# Schematic.net
KiCad netlist of a schematic drawn in EAGLE
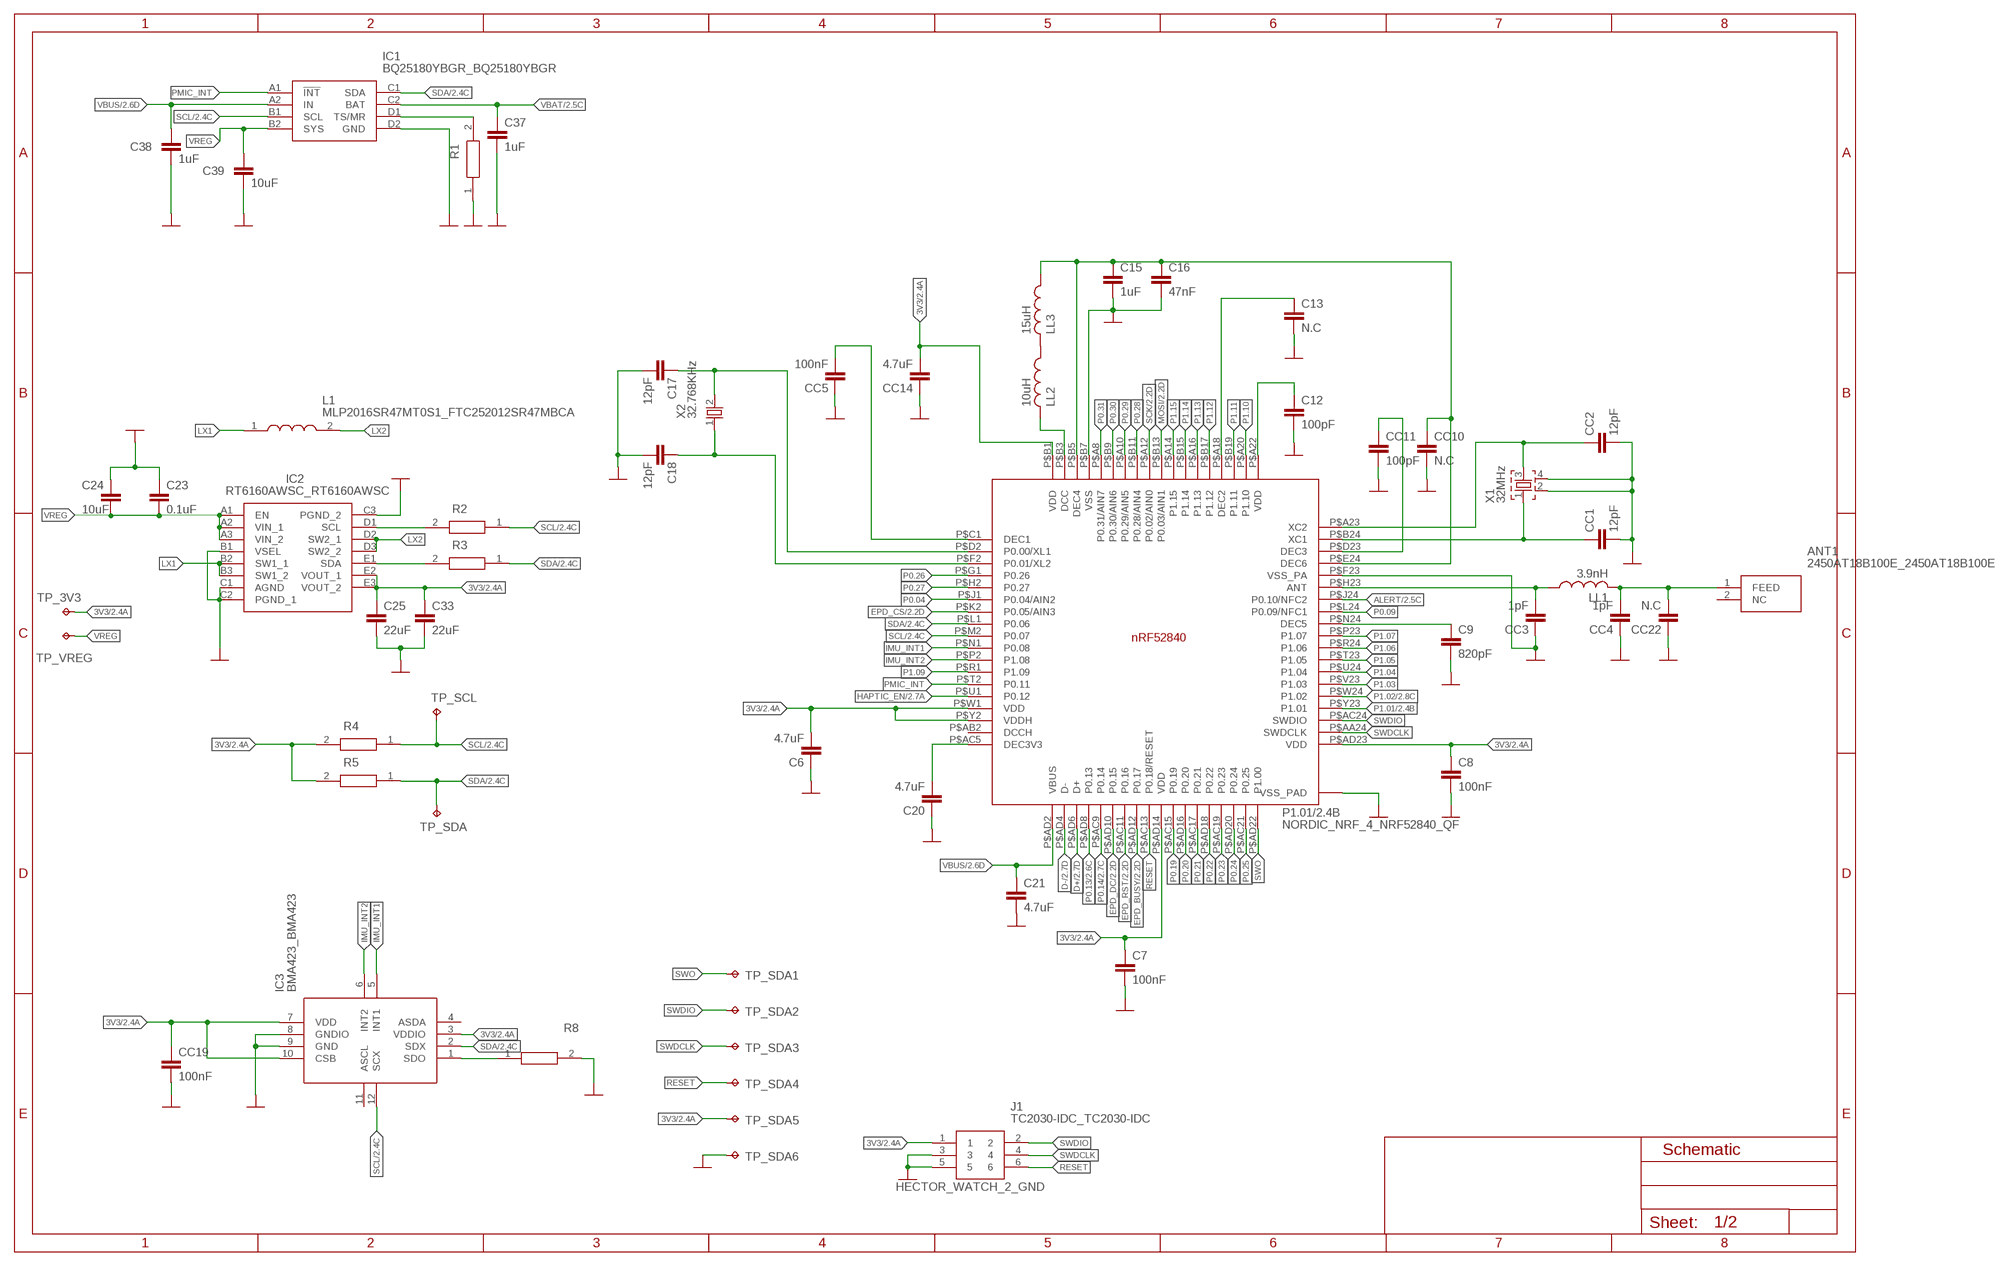
[diagram p0: schematic, sheet 1]
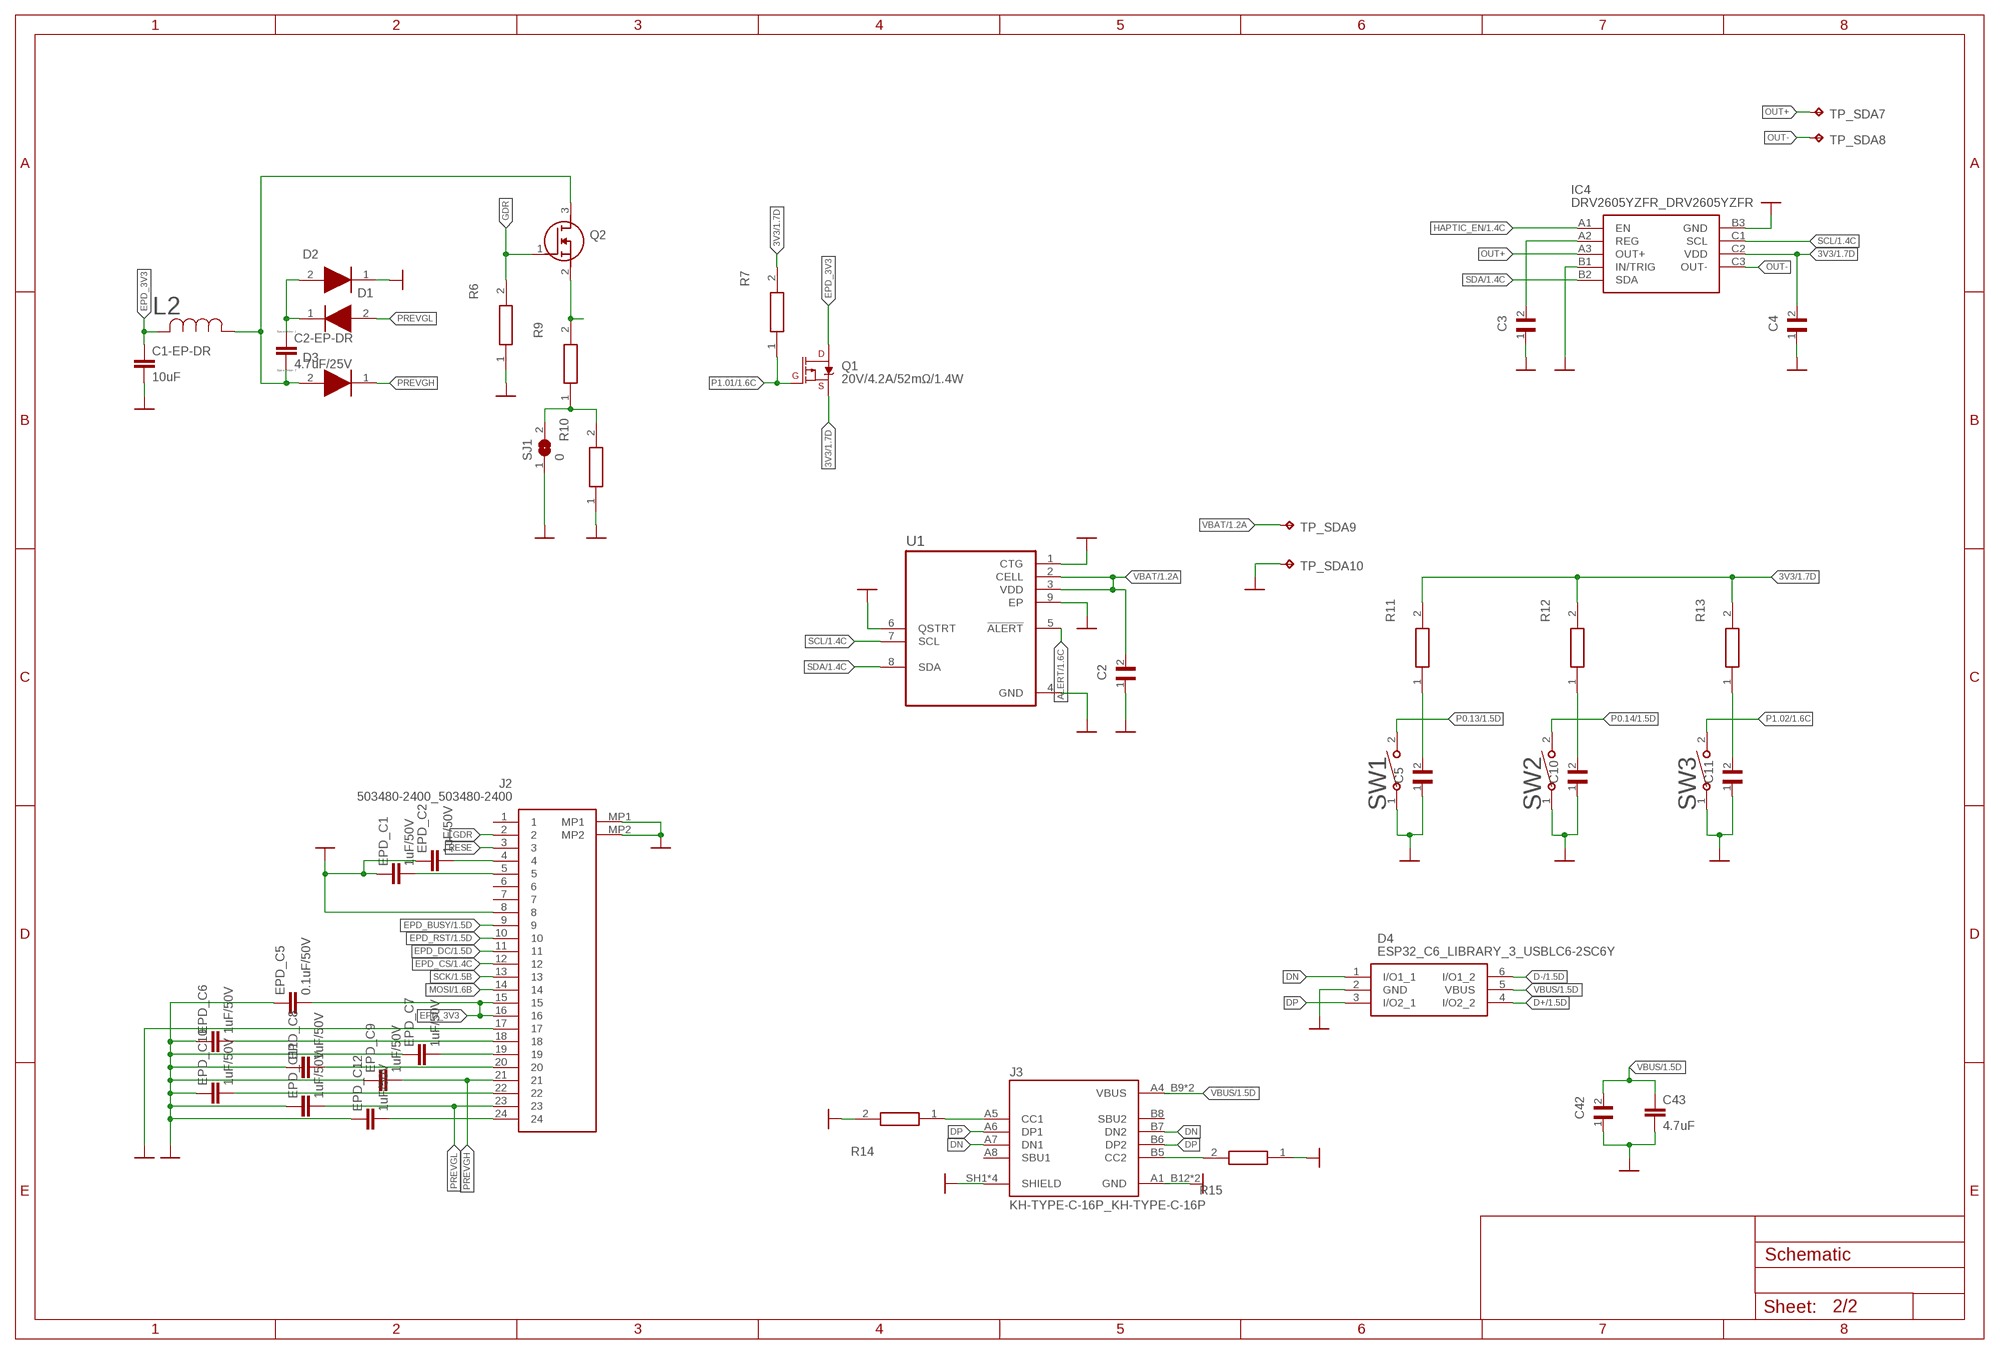
[diagram p1: schematic, sheet 2]

(export (version "E")
  (design (tool "Eeschema 10.0.6"))
  (components
    (comp (ref "ANT1")
      (value "2450AT18B100E_2450AT18B100E")
      (footprint "eagle-import:2450AT18B100E_ANTC3216X140N")
      (fields
        (field (name "ARROW_PART_NUMBER") "2450AT18B100E")
        (field (name "MOUSER_PART_NUMBER") "609-2450AT18B100E")
      )
      (libsource (lib "eagle-import") (part "2450AT18B100E_2450AT18B100E"))
    )
    (comp (ref "C6")
      (value "4.7uF")
      (footprint "eagle-import:NORDIC_NRF_3_RESC0402_M")
      (libsource (lib "eagle-import") (part "NORDIC_NRF_3_CAPACITOR_0402_M"))
    )
    (comp (ref "C7")
      (value "100nF")
      (footprint "eagle-import:NORDIC_NRF_3_RESC0402_M")
      (libsource (lib "eagle-import") (part "NORDIC_NRF_3_CAPACITOR_0402_M"))
    )
    (comp (ref "C8")
      (value "100nF")
      (footprint "eagle-import:NORDIC_NRF_3_RESC0402_M")
      (libsource (lib "eagle-import") (part "NORDIC_NRF_3_CAPACITOR_0402_M"))
    )
    (comp (ref "C9")
      (value "820pF")
      (footprint "eagle-import:NORDIC_NRF_3_RESC0402_M")
      (libsource (lib "eagle-import") (part "NORDIC_NRF_3_CAPACITOR_0402_M"))
    )
    (comp (ref "C12")
      (value "100pF")
      (footprint "eagle-import:NORDIC_NRF_3_RESC0402_M")
      (libsource (lib "eagle-import") (part "NORDIC_NRF_3_CAPACITOR_0402_M"))
    )
    (comp (ref "C13")
      (value "N.C")
      (footprint "eagle-import:NORDIC_NRF_3_RESC0402_M")
      (libsource (lib "eagle-import") (part "NORDIC_NRF_3_CAPACITOR_0402_M"))
    )
    (comp (ref "C15")
      (value "1uF")
      (footprint "eagle-import:NORDIC_NRF_3_RESC0402_M")
      (libsource (lib "eagle-import") (part "NORDIC_NRF_3_CAPACITOR_0402_M"))
    )
    (comp (ref "C16")
      (value "47nF")
      (footprint "eagle-import:NORDIC_NRF_3_RESC0402_M")
      (libsource (lib "eagle-import") (part "NORDIC_NRF_3_CAPACITOR_0402_M"))
    )
    (comp (ref "C17")
      (value "12pF")
      (footprint "eagle-import:NORDIC_NRF_3_RESC0402_M")
      (libsource (lib "eagle-import") (part "NORDIC_NRF_3_CAPACITOR_0402_M"))
    )
    (comp (ref "C18")
      (value "12pF")
      (footprint "eagle-import:NORDIC_NRF_3_RESC0402_M")
      (libsource (lib "eagle-import") (part "NORDIC_NRF_3_CAPACITOR_0402_M"))
    )
    (comp (ref "C20")
      (value "4.7uF")
      (footprint "eagle-import:NORDIC_NRF_3_RESC0402_M")
      (libsource (lib "eagle-import") (part "NORDIC_NRF_3_CAPACITOR_0402_M"))
    )
    (comp (ref "C21")
      (value "4.7uF")
      (footprint "eagle-import:NORDIC_NRF_3_RESC0402_M")
      (libsource (lib "eagle-import") (part "NORDIC_NRF_3_CAPACITOR_0402_M"))
    )
    (comp (ref "C23")
      (value "0.1uF")
      (footprint "eagle-import:NORDIC_NRF_3_RESC0402_M")
      (libsource (lib "eagle-import") (part "NORDIC_NRF_3_CAPACITOR_0402_M"))
    )
    (comp (ref "C24")
      (value "10uF")
      (footprint "eagle-import:NORDIC_NRF_3_RESC0402_M")
      (libsource (lib "eagle-import") (part "NORDIC_NRF_3_CAPACITOR_0402_M"))
    )
    (comp (ref "C25")
      (value "22uF")
      (footprint "eagle-import:NORDIC_NRF_3_RESC0402_M")
      (libsource (lib "eagle-import") (part "NORDIC_NRF_3_CAPACITOR_0402_M"))
    )
    (comp (ref "C33")
      (value "22uF")
      (footprint "eagle-import:NORDIC_NRF_3_RESC0402_M")
      (libsource (lib "eagle-import") (part "NORDIC_NRF_3_CAPACITOR_0402_M"))
    )
    (comp (ref "C37")
      (value "1uF")
      (footprint "eagle-import:NORDIC_NRF_3_RESC0402_M")
      (libsource (lib "eagle-import") (part "NORDIC_NRF_3_CAPACITOR_0402_M"))
    )
    (comp (ref "C38")
      (value "1uF")
      (footprint "eagle-import:NORDIC_NRF_3_RESC0402_M")
      (libsource (lib "eagle-import") (part "NORDIC_NRF_3_CAPACITOR_0402_M"))
    )
    (comp (ref "C39")
      (value "10uF")
      (footprint "eagle-import:NORDIC_NRF_3_RESC0402_M")
      (libsource (lib "eagle-import") (part "NORDIC_NRF_3_CAPACITOR_0402_M"))
    )
    (comp (ref "CC1")
      (value "12pF")
      (footprint "eagle-import:NORDIC_NRF_3_RESC0402_M")
      (libsource (lib "eagle-import") (part "NORDIC_NRF_3_CAPACITOR_0402_M"))
    )
    (comp (ref "CC2")
      (value "12pF")
      (footprint "eagle-import:NORDIC_NRF_3_RESC0402_M")
      (libsource (lib "eagle-import") (part "NORDIC_NRF_3_CAPACITOR_0402_M"))
    )
    (comp (ref "CC3")
      (value "1pF")
      (footprint "eagle-import:NORDIC_NRF_3_RESC0402_M")
      (libsource (lib "eagle-import") (part "NORDIC_NRF_3_CAPACITOR_0402_M"))
    )
    (comp (ref "CC4")
      (value "1pF")
      (footprint "eagle-import:NORDIC_NRF_3_RESC0402_M")
      (libsource (lib "eagle-import") (part "NORDIC_NRF_3_CAPACITOR_0402_M"))
    )
    (comp (ref "CC5")
      (value "100nF")
      (footprint "eagle-import:NORDIC_NRF_3_RESC0402_M")
      (libsource (lib "eagle-import") (part "NORDIC_NRF_3_CAPACITOR_0402_M"))
    )
    (comp (ref "CC10")
      (value "N.C")
      (footprint "eagle-import:NORDIC_NRF_3_RESC0402_M")
      (libsource (lib "eagle-import") (part "NORDIC_NRF_3_CAPACITOR_0402_M"))
    )
    (comp (ref "CC11")
      (value "100pF")
      (footprint "eagle-import:NORDIC_NRF_3_RESC0402_M")
      (libsource (lib "eagle-import") (part "NORDIC_NRF_3_CAPACITOR_0402_M"))
    )
    (comp (ref "CC14")
      (value "4.7uF")
      (footprint "eagle-import:NORDIC_NRF_3_RESC0402_M")
      (libsource (lib "eagle-import") (part "NORDIC_NRF_3_CAPACITOR_0402_M"))
    )
    (comp (ref "CC19")
      (value "100nF")
      (footprint "eagle-import:NORDIC_NRF_3_RESC0402_M")
      (libsource (lib "eagle-import") (part "NORDIC_NRF_3_CAPACITOR_0402_M"))
    )
    (comp (ref "CC22")
      (value "N.C")
      (footprint "eagle-import:NORDIC_NRF_3_RESC0402_M")
      (libsource (lib "eagle-import") (part "NORDIC_NRF_3_CAPACITOR_0402_M"))
    )
    (comp (ref "IC1")
      (value "BQ25180YBGR_BQ25180YBGR")
      (footprint "eagle-import:BQ25180YBGR_BGA8C40P2X4_100X155X50")
      (fields
        (field (name "ARROW_PART_NUMBER") "BQ25180YBGR")
        (field (name "MOUSER_PART_NUMBER") "595-BQ25180YBGR")
      )
      (libsource (lib "eagle-import") (part "BQ25180YBGR_BQ25180YBGR"))
    )
    (comp (ref "IC2")
      (value "RT6160AWSC_RT6160AWSC")
      (footprint "eagle-import:RT6160AWSC_BGA15C40P3X5_140X230X60")
      (fields
        (field (name "MANUFACTURER_PART_NUMBER") "RT6160AWSC")
        (field (name "MOUSER_PART_NUMBER") "835-RT6160AWSC")
      )
      (libsource (lib "eagle-import") (part "RT6160AWSC_RT6160AWSC"))
    )
    (comp (ref "IC3")
      (value "BMA423_BMA423")
      (footprint "eagle-import:BMA423_BMA423")
      (fields (field (name "ARROW_PART_NUMBER") "BMA423") (field (name "MOUSER_PART_NUMBER") "262-BMA423"))
      (libsource (lib "eagle-import") (part "BMA423_BMA423"))
    )
    (comp (ref "J1")
      (value "TC2030-IDC_TC2030-IDC")
      (footprint "eagle-import:TC2030-IDC_TC2030IDC")
      (fields (field (name "MANUFACTURER_PART_NUMBER") "TC2030-IDC"))
      (libsource (lib "eagle-import") (part "TC2030-IDC_TC2030-IDC"))
    )
    (comp (ref "L1")
      (value "MLP2016SR47MT0S1_FTC252012SR47MBCA")
      (footprint "eagle-import:MLP2016SR47MT0S1_INDC2016X100N")
      (fields (field (name "MANUFACTURER_PART_NUMBER") "FTC252012SR47MBCA"))
      (libsource (lib "eagle-import") (part "MLP2016SR47MT0S1_FTC252012SR47MBCA"))
    )
    (comp (ref "LL1")
      (value "3.9nH")
      (footprint "eagle-import:NORDIC_NRF_2_RESC0402_M")
      (libsource (lib "eagle-import") (part "NORDIC_NRF_2_INDUCTOR_0402_M"))
    )
    (comp (ref "LL2")
      (value "10uH")
      (footprint "eagle-import:NORDIC_NRF_2_RESC0402_M")
      (libsource (lib "eagle-import") (part "NORDIC_NRF_2_INDUCTOR_0402_M"))
    )
    (comp (ref "LL3")
      (value "15uH")
      (footprint "eagle-import:NORDIC_NRF_2_RESC0402_M")
      (libsource (lib "eagle-import") (part "NORDIC_NRF_2_INDUCTOR_0402_M"))
    )
    (comp (ref "P1.01/2.4B")
      (value "NORDIC_NRF_4_NRF52840_QF")
      (footprint "eagle-import:NORDIC_NRF_4_AQFN50P700X700X85_HS-74N")
      (libsource (lib "eagle-import") (part "NORDIC_NRF_4_NRF52840_QF"))
    )
    (comp (ref "R1")
      (value "10K")
      (footprint "eagle-import:CPF0201D7K68C1_0201")
      (libsource (lib "eagle-import") (part "CPF0201D7K68C1_CPF0201D7K68C1"))
    )
    (comp (ref "R2")
      (value "CPF0201D7K68C1_CPF0201D7K68C1")
      (footprint "eagle-import:CPF0201D7K68C1_0201")
      (libsource (lib "eagle-import") (part "CPF0201D7K68C1_CPF0201D7K68C1"))
    )
    (comp (ref "R3")
      (value "CPF0201D7K68C1_CPF0201D7K68C1")
      (footprint "eagle-import:CPF0201D7K68C1_0201")
      (libsource (lib "eagle-import") (part "CPF0201D7K68C1_CPF0201D7K68C1"))
    )
    (comp (ref "R4")
      (value "CPF0201D7K68C1_CPF0201D7K68C1")
      (footprint "eagle-import:CPF0201D7K68C1_0201")
      (libsource (lib "eagle-import") (part "CPF0201D7K68C1_CPF0201D7K68C1"))
    )
    (comp (ref "R5")
      (value "CPF0201D7K68C1_CPF0201D7K68C1")
      (footprint "eagle-import:CPF0201D7K68C1_0201")
      (libsource (lib "eagle-import") (part "CPF0201D7K68C1_CPF0201D7K68C1"))
    )
    (comp (ref "R8")
      (value "CPF0201D7K68C1_CPF0201D7K68C1")
      (footprint "eagle-import:CPF0201D7K68C1_0201")
      (libsource (lib "eagle-import") (part "CPF0201D7K68C1_CPF0201D7K68C1"))
    )
    (comp (ref "TP_3V3")
      (value "HECTOR_WATCH_1_TPTP20R")
      (footprint "eagle-import:HECTOR_WATCH_1_TP20R")
      (libsource (lib "eagle-import") (part "HECTOR_WATCH_1_TPTP20R"))
    )
    (comp (ref "TP_SCL")
      (value "HECTOR_WATCH_1_TPTP20R")
      (footprint "eagle-import:HECTOR_WATCH_1_TP20R")
      (libsource (lib "eagle-import") (part "HECTOR_WATCH_1_TPTP20R"))
    )
    (comp (ref "TP_SDA")
      (value "HECTOR_WATCH_1_TPTP20R")
      (footprint "eagle-import:HECTOR_WATCH_1_TP20R")
      (libsource (lib "eagle-import") (part "HECTOR_WATCH_1_TPTP20R"))
    )
    (comp (ref "TP_SDA1")
      (value "HECTOR_WATCH_1_TPTP20R")
      (footprint "eagle-import:HECTOR_WATCH_1_TP20R")
      (libsource (lib "eagle-import") (part "HECTOR_WATCH_1_TPTP20R"))
    )
    (comp (ref "TP_SDA2")
      (value "HECTOR_WATCH_1_TPTP20R")
      (footprint "eagle-import:HECTOR_WATCH_1_TP20R")
      (libsource (lib "eagle-import") (part "HECTOR_WATCH_1_TPTP20R"))
    )
    (comp (ref "TP_SDA3")
      (value "HECTOR_WATCH_1_TPTP20R")
      (footprint "eagle-import:HECTOR_WATCH_1_TP20R")
      (libsource (lib "eagle-import") (part "HECTOR_WATCH_1_TPTP20R"))
    )
    (comp (ref "TP_SDA4")
      (value "HECTOR_WATCH_1_TPTP20R")
      (footprint "eagle-import:HECTOR_WATCH_1_TP20R")
      (libsource (lib "eagle-import") (part "HECTOR_WATCH_1_TPTP20R"))
    )
    (comp (ref "TP_SDA5")
      (value "HECTOR_WATCH_1_TPTP20R")
      (footprint "eagle-import:HECTOR_WATCH_1_TP20R")
      (libsource (lib "eagle-import") (part "HECTOR_WATCH_1_TPTP20R"))
    )
    (comp (ref "TP_SDA6")
      (value "HECTOR_WATCH_1_TPTP20R")
      (footprint "eagle-import:HECTOR_WATCH_1_TP20R")
      (libsource (lib "eagle-import") (part "HECTOR_WATCH_1_TPTP20R"))
    )
    (comp (ref "TP_VREG")
      (value "HECTOR_WATCH_1_TPTP20R")
      (footprint "eagle-import:HECTOR_WATCH_1_TP20R")
      (libsource (lib "eagle-import") (part "HECTOR_WATCH_1_TPTP20R"))
    )
    (comp (ref "X1")
      (value "32MHz")
      (footprint "eagle-import:NORDIC_NRF_BT-XTAL_2016_N")
      (libsource (lib "eagle-import") (part "NORDIC_NRF_XTAL_32MHZ"))
    )
    (comp (ref "X2")
      (value "32.768KHz")
      (footprint "eagle-import:NORDIC_NRF_1_XTAL_3215_N")
      (libsource (lib "eagle-import") (part "NORDIC_NRF_1_XTAL_32KHZ"))
    )
    (comp (ref "C1-EP-DR")
      (value "10uF")
      (footprint "eagle-import:NORDIC_NRF_3_RESC0402_M")
      (libsource (lib "eagle-import") (part "NORDIC_NRF_3_CAPACITOR_0402_M"))
    )
    (comp (ref "C2")
      (value "GRM011R60J152KE01L_1_GRM011R60J152KE01L")
      (footprint "eagle-import:GRM011R60J152KE01L_1_0201")
      (libsource (lib "eagle-import") (part "GRM011R60J152KE01L_1_GRM011R60J152KE01L"))
    )
    (comp (ref "C2-EP-DR")
      (value "4.7uF/25V")
      (footprint "eagle-import:ESP32_C6_LIBRARY_1_ESP32_WROVER_EAGLE-LTSPICE_C0402")
      (libsource (lib "eagle-import") (part "ESP32_C6_LIBRARY_1_ESP32_WROVER_EAGLE-LTSPICE_CC0402"))
    )
    (comp (ref "C3")
      (value "1uF")
      (footprint "eagle-import:GRM011R60J152KE01L_1_0201")
      (libsource (lib "eagle-import") (part "GRM011R60J152KE01L_1_GRM011R60J152KE01L"))
    )
    (comp (ref "C4")
      (value "0.1uF")
      (footprint "eagle-import:GRM011R60J152KE01L_1_0201")
      (libsource (lib "eagle-import") (part "GRM011R60J152KE01L_1_GRM011R60J152KE01L"))
    )
    (comp (ref "C5")
      (value "GRM011R60J152KE01L_1_GRM011R60J152KE01L")
      (footprint "eagle-import:GRM011R60J152KE01L_1_0201")
      (libsource (lib "eagle-import") (part "GRM011R60J152KE01L_1_GRM011R60J152KE01L"))
    )
    (comp (ref "C10")
      (value "GRM011R60J152KE01L_1_GRM011R60J152KE01L")
      (footprint "eagle-import:GRM011R60J152KE01L_1_0201")
      (libsource (lib "eagle-import") (part "GRM011R60J152KE01L_1_GRM011R60J152KE01L"))
    )
    (comp (ref "C11")
      (value "GRM011R60J152KE01L_1_GRM011R60J152KE01L")
      (footprint "eagle-import:GRM011R60J152KE01L_1_0201")
      (libsource (lib "eagle-import") (part "GRM011R60J152KE01L_1_GRM011R60J152KE01L"))
    )
    (comp (ref "C42")
      (value "GRM011R60J152KE01L_1_GRM011R60J152KE01L")
      (footprint "eagle-import:GRM011R60J152KE01L_1_0201")
      (libsource (lib "eagle-import") (part "GRM011R60J152KE01L_1_GRM011R60J152KE01L"))
    )
    (comp (ref "C43")
      (value "4.7uF")
      (footprint "eagle-import:NORDIC_NRF_3_RESC0402_M")
      (libsource (lib "eagle-import") (part "NORDIC_NRF_3_CAPACITOR_0402_M"))
    )
    (comp (ref "D1")
      (value "ESP32_C6_LIBRARY_5_MBR0530")
      (footprint "eagle-import:ESP32_C6_LIBRARY_5_SOD3716X135N")
      (fields (field (name "MF") "ON Semiconductor") (field (name "MP") "MBR0530"))
      (libsource (lib "eagle-import") (part "ESP32_C6_LIBRARY_5_MBR0530"))
    )
    (comp (ref "D2")
      (value "ESP32_C6_LIBRARY_5_MBR0530")
      (footprint "eagle-import:ESP32_C6_LIBRARY_5_SOD3716X135N")
      (fields (field (name "MF") "ON Semiconductor") (field (name "MP") "MBR0530"))
      (libsource (lib "eagle-import") (part "ESP32_C6_LIBRARY_5_MBR0530"))
    )
    (comp (ref "D3")
      (value "ESP32_C6_LIBRARY_5_MBR0530")
      (footprint "eagle-import:ESP32_C6_LIBRARY_5_SOD3716X135N")
      (fields (field (name "MF") "ON Semiconductor") (field (name "MP") "MBR0530"))
      (libsource (lib "eagle-import") (part "ESP32_C6_LIBRARY_5_MBR0530"))
    )
    (comp (ref "D4")
      (value "ESP32_C6_LIBRARY_3_USBLC6-2SC6Y")
      (footprint "eagle-import:ESP32_C6_LIBRARY_3_SOT95P280X145-6N")
      (fields (field (name "MF") "STMicroelectronics") (field (name "MP") "USBLC6-2SC6Y"))
      (libsource (lib "eagle-import") (part "ESP32_C6_LIBRARY_3_USBLC6-2SC6Y"))
    )
    (comp (ref "EPD_C1")
      (value "1uF/50V")
      (footprint "eagle-import:NORDIC_NRF_3_RESC0402_M")
      (libsource (lib "eagle-import") (part "NORDIC_NRF_3_CAPACITOR_0402_M"))
    )
    (comp (ref "EPD_C2")
      (value "1uF/50V")
      (footprint "eagle-import:NORDIC_NRF_3_RESC0402_M")
      (libsource (lib "eagle-import") (part "NORDIC_NRF_3_CAPACITOR_0402_M"))
    )
    (comp (ref "EPD_C5")
      (value "0.1uF/50V")
      (footprint "eagle-import:NORDIC_NRF_3_RESC0402_M")
      (libsource (lib "eagle-import") (part "NORDIC_NRF_3_CAPACITOR_0402_M"))
    )
    (comp (ref "EPD_C6")
      (value "1uF/50V")
      (footprint "eagle-import:NORDIC_NRF_3_RESC0402_M")
      (libsource (lib "eagle-import") (part "NORDIC_NRF_3_CAPACITOR_0402_M"))
    )
    (comp (ref "EPD_C7")
      (value "1uF/50V")
      (footprint "eagle-import:NORDIC_NRF_3_RESC0402_M")
      (libsource (lib "eagle-import") (part "NORDIC_NRF_3_CAPACITOR_0402_M"))
    )
    (comp (ref "EPD_C8")
      (value "1uF/50V")
      (footprint "eagle-import:NORDIC_NRF_3_RESC0402_M")
      (libsource (lib "eagle-import") (part "NORDIC_NRF_3_CAPACITOR_0402_M"))
    )
    (comp (ref "EPD_C9")
      (value "1uF/50V")
      (footprint "eagle-import:NORDIC_NRF_3_RESC0402_M")
      (libsource (lib "eagle-import") (part "NORDIC_NRF_3_CAPACITOR_0402_M"))
    )
    (comp (ref "EPD_C10")
      (value "1uF/50V")
      (footprint "eagle-import:NORDIC_NRF_3_RESC0402_M")
      (libsource (lib "eagle-import") (part "NORDIC_NRF_3_CAPACITOR_0402_M"))
    )
    (comp (ref "EPD_C11")
      (value "1uF/50V")
      (footprint "eagle-import:NORDIC_NRF_3_RESC0402_M")
      (libsource (lib "eagle-import") (part "NORDIC_NRF_3_CAPACITOR_0402_M"))
    )
    (comp (ref "EPD_C12")
      (value "1uF/50V")
      (footprint "eagle-import:NORDIC_NRF_3_RESC0402_M")
      (libsource (lib "eagle-import") (part "NORDIC_NRF_3_CAPACITOR_0402_M"))
    )
    (comp (ref "IC4")
      (value "DRV2605YZFR_DRV2605YZFR")
      (footprint "eagle-import:DRV2605YZFR_BGA9C50P3X3_144X144X62")
      (fields (field (name "ARROW_PART_NUMBER") "DRV2605YZFR"))
      (libsource (lib "eagle-import") (part "DRV2605YZFR_DRV2605YZFR"))
    )
    (comp (ref "J2")
      (value "503480-2400_503480-2400")
      (footprint "eagle-import:503480-2400_5034802400")
      (fields
        (field (name "MANUFACTURER_PART_NUMBER") "503480-2400")
        (field (name "MOUSER_PART_NUMBER") "538-503480-2400")
      )
      (libsource (lib "eagle-import") (part "503480-2400_503480-2400"))
    )
    (comp (ref "J3")
      (value "KH-TYPE-C-16P_KH-TYPE-C-16P")
      (footprint "eagle-import:KH-TYPE-C-16P_KINGHELM_KH-TYPE-C-16P")
      (fields (field (name "MF") "kinghelm") (field (name "MP") "KH-TYPE-C-16P"))
      (libsource (lib "eagle-import") (part "KH-TYPE-C-16P_KH-TYPE-C-16P"))
    )
    (comp (ref "L2")
      (value "ESP32_C6_LIBRARY_2_744043680IND_4828-WE-TPC_WRE")
      (footprint "eagle-import:ESP32_C6_LIBRARY_2_IND_4828-WE-TPC_WRE")
      (fields
        (field (name "MANUFACTURER_PART_NUMBER") "744043680")
        (field (name "COPYRIGHT") "Copyright (C) 2024 Ultra Librarian. All rights reserved.")
      )
      (libsource (lib "eagle-import") (part "ESP32_C6_LIBRARY_2_744043680IND_4828-WE-TPC_WRE"))
    )
    (comp (ref "Q1")
      (value "20V/4.2A/52mΩ/1.4W")
      (footprint "eagle-import:ESP32_C6_LIBRARY_4_ESP32_C6_LIBRARY_4_ESP32_C6_LIBRARY_4_ESP32_C6_LIBRARY_4_ESP32_WROVER_SPARKFUN-DISCRETESEMI_SOT23-3")
      (libsource (lib "eagle-import") (part "ESP32_C6_LIBRARY_4_ESP32_WROVER_SPARKFUN-DISCRETESEMI_MOSFET_PCH-DMG2305UX-7"))
    )
    (comp (ref "Q2")
      (value "ESP32_C6_LIBRARY_6_SI1308EDL-T1-GE3")
      (footprint "eagle-import:ESP32_C6_LIBRARY_6_SOT65P210X110-3N")
      (fields (field (name "MF") "Vishay Siliconix") (field (name "MP") "SI1308EDL-T1-GE3"))
      (libsource (lib "eagle-import") (part "ESP32_C6_LIBRARY_6_SI1308EDL-T1-GE3"))
    )
    (comp (ref "R6")
      (value "CPF0201D7K68C1_CPF0201D7K68C1")
      (footprint "eagle-import:CPF0201D7K68C1_0201")
      (libsource (lib "eagle-import") (part "CPF0201D7K68C1_CPF0201D7K68C1"))
    )
    (comp (ref "R7")
      (value "CPF0201D7K68C1_CPF0201D7K68C1")
      (footprint "eagle-import:CPF0201D7K68C1_0201")
      (libsource (lib "eagle-import") (part "CPF0201D7K68C1_CPF0201D7K68C1"))
    )
    (comp (ref "R9")
      (value "CPF0201D7K68C1_CPF0201D7K68C1")
      (footprint "eagle-import:CPF0201D7K68C1_0201")
      (libsource (lib "eagle-import") (part "CPF0201D7K68C1_CPF0201D7K68C1"))
    )
    (comp (ref "R10")
      (value "CPF0201D7K68C1_CPF0201D7K68C1")
      (footprint "eagle-import:CPF0201D7K68C1_0201")
      (libsource (lib "eagle-import") (part "CPF0201D7K68C1_CPF0201D7K68C1"))
    )
    (comp (ref "R11")
      (value "CPF0201D7K68C1_CPF0201D7K68C1")
      (footprint "eagle-import:CPF0201D7K68C1_0201")
      (libsource (lib "eagle-import") (part "CPF0201D7K68C1_CPF0201D7K68C1"))
    )
    (comp (ref "R12")
      (value "CPF0201D7K68C1_CPF0201D7K68C1")
      (footprint "eagle-import:CPF0201D7K68C1_0201")
      (libsource (lib "eagle-import") (part "CPF0201D7K68C1_CPF0201D7K68C1"))
    )
    (comp (ref "R13")
      (value "CPF0201D7K68C1_CPF0201D7K68C1")
      (footprint "eagle-import:CPF0201D7K68C1_0201")
      (libsource (lib "eagle-import") (part "CPF0201D7K68C1_CPF0201D7K68C1"))
    )
    (comp (ref "R14")
      (value "CPF0201D7K68C1_CPF0201D7K68C1")
      (footprint "eagle-import:CPF0201D7K68C1_0201")
      (libsource (lib "eagle-import") (part "CPF0201D7K68C1_CPF0201D7K68C1"))
    )
    (comp (ref "R15")
      (value "CPF0201D7K68C1_CPF0201D7K68C1")
      (footprint "eagle-import:CPF0201D7K68C1_0201")
      (libsource (lib "eagle-import") (part "CPF0201D7K68C1_CPF0201D7K68C1"))
    )
    (comp (ref "SJ1")
      (value "0")
      (footprint "eagle-import:ESP32_C6_LIBRARY_7_JUMPER_SJ")
      (libsource (lib "eagle-import") (part "ESP32_C6_LIBRARY_7_JUMPER_SJ"))
    )
    (comp (ref "SW1")
      (value "2025-10-22_07-23-44_LIBRARY_EVP-AKE31ASW_EVP-AKE31A_PAN")
      (footprint "eagle-import:2025-10-22_07-23-44_LIBRARY_SW_EVP-AKE31A_PAN")
      (fields
        (field (name "MANUFACTURER_PART_NUMBER") "EVP-AKE31A")
        (field (name "COPYRIGHT") "Copyright (C) 2025 Ultra Librarian. All rights reserved.")
      )
      (libsource (lib "eagle-import") (part "2025-10-22_07-23-44_LIBRARY_EVP-AKE31ASW_EVP-AKE31A_PAN"))
    )
    (comp (ref "SW2")
      (value "2025-10-22_07-23-44_LIBRARY_EVP-AKE31ASW_EVP-AKE31A_PAN")
      (footprint "eagle-import:2025-10-22_07-23-44_LIBRARY_SW_EVP-AKE31A_PAN")
      (fields
        (field (name "MANUFACTURER_PART_NUMBER") "EVP-AKE31A")
        (field (name "COPYRIGHT") "Copyright (C) 2025 Ultra Librarian. All rights reserved.")
      )
      (libsource (lib "eagle-import") (part "2025-10-22_07-23-44_LIBRARY_EVP-AKE31ASW_EVP-AKE31A_PAN"))
    )
    (comp (ref "SW3")
      (value "2025-10-22_07-23-44_LIBRARY_EVP-AKE31ASW_EVP-AKE31A_PAN")
      (footprint "eagle-import:2025-10-22_07-23-44_LIBRARY_SW_EVP-AKE31A_PAN")
      (fields
        (field (name "MANUFACTURER_PART_NUMBER") "EVP-AKE31A")
        (field (name "COPYRIGHT") "Copyright (C) 2025 Ultra Librarian. All rights reserved.")
      )
      (libsource (lib "eagle-import") (part "2025-10-22_07-23-44_LIBRARY_EVP-AKE31ASW_EVP-AKE31A_PAN"))
    )
    (comp (ref "TP_SDA7")
      (value "HECTOR_WATCH_1_TPTP20R")
      (footprint "eagle-import:HECTOR_WATCH_1_TP20R")
      (libsource (lib "eagle-import") (part "HECTOR_WATCH_1_TPTP20R"))
    )
    (comp (ref "TP_SDA8")
      (value "HECTOR_WATCH_1_TPTP20R")
      (footprint "eagle-import:HECTOR_WATCH_1_TP20R")
      (libsource (lib "eagle-import") (part "HECTOR_WATCH_1_TPTP20R"))
    )
    (comp (ref "TP_SDA9")
      (value "HECTOR_WATCH_1_TPTP20R")
      (footprint "eagle-import:HECTOR_WATCH_1_TP20R")
      (libsource (lib "eagle-import") (part "HECTOR_WATCH_1_TPTP20R"))
    )
    (comp (ref "TP_SDA10")
      (value "HECTOR_WATCH_1_TPTP20R")
      (footprint "eagle-import:HECTOR_WATCH_1_TP20R")
      (libsource (lib "eagle-import") (part "HECTOR_WATCH_1_TPTP20R"))
    )
    (comp (ref "U1")
      (value "ESP32_C6_LIBRARY_MAX17048G+T10")
      (footprint "eagle-import:ESP32_C6_LIBRARY_SON50P200X200X80-9N")
      (fields (field (name "MF") "Analog Devices") (field (name "MP") "MAX17048G+T10"))
      (libsource (lib "eagle-import") (part "ESP32_C6_LIBRARY_MAX17048G+T10"))
    )
  )
  (nets
    (net (code "1") (name "3V3{slash}1.7D") (class "Default")
      (node (ref "C4") (pin "2") (pinfunction "2_2") (pintype "passive"))
      (node (ref "IC4") (pin "C2") (pinfunction "VDD_C2") (pintype "bidirectional"))
      (node (ref "Q1") (pin "2") (pinfunction "S_2") (pintype "bidirectional"))
      (node (ref "R11") (pin "2") (pinfunction "2_2") (pintype "bidirectional"))
      (node (ref "R12") (pin "2") (pinfunction "2_2") (pintype "bidirectional"))
      (node (ref "R13") (pin "2") (pinfunction "2_2") (pintype "bidirectional"))
      (node (ref "R7") (pin "2") (pinfunction "2_2") (pintype "bidirectional"))
    )
    (net (code "2") (name "3V3{slash}2.4A") (class "Default")
      (node (ref "C25") (pin "1") (pinfunction "1_1") (pintype "passive"))
      (node (ref "C33") (pin "1") (pinfunction "1_1") (pintype "passive"))
      (node (ref "C6") (pin "2") (pinfunction "2_2") (pintype "passive"))
      (node (ref "C7") (pin "1") (pinfunction "1_1") (pintype "passive"))
      (node (ref "C8") (pin "1") (pinfunction "1_1") (pintype "passive"))
      (node (ref "CC14") (pin "2") (pinfunction "2_2") (pintype "passive"))
      (node (ref "CC19") (pin "1") (pinfunction "1_1") (pintype "passive"))
      (node (ref "IC2") (pin "E2") (pinfunction "VOUT_1_E2") (pintype "bidirectional"))
      (node (ref "IC2") (pin "E3") (pinfunction "VOUT_2_E3") (pintype "bidirectional"))
      (node (ref "IC3") (pin "10") (pinfunction "CSB_10") (pintype "bidirectional"))
      (node (ref "IC3") (pin "3") (pinfunction "VDDIO_3") (pintype "bidirectional"))
      (node (ref "IC3") (pin "7") (pinfunction "VDD_7") (pintype "bidirectional"))
      (node (ref "J1") (pin "1") (pinfunction "1_1") (pintype "bidirectional"))
      (node (ref "P1.01/2.4B") (pin "P$AD14") (pinfunction "VDD_P$AD14") (pintype "power_in"))
      (node (ref "P1.01/2.4B") (pin "P$AD23") (pinfunction "VDD_P$AD23") (pintype "power_in"))
      (node (ref "P1.01/2.4B") (pin "P$B1") (pinfunction "VDD_P$B1") (pintype "power_in"))
      (node (ref "P1.01/2.4B") (pin "P$W1") (pinfunction "VDD_P$W1") (pintype "power_in"))
      (node (ref "P1.01/2.4B") (pin "P$Y2") (pinfunction "VDDH_P$Y2") (pintype "power_in"))
      (node (ref "R4") (pin "2") (pinfunction "2_2") (pintype "bidirectional"))
      (node (ref "R5") (pin "2") (pinfunction "2_2") (pintype "bidirectional"))
      (node (ref "TP_3V3") (pin "TP") (pinfunction "TP_TP") (pintype "input"))
      (node (ref "TP_SDA5") (pin "TP") (pinfunction "TP_TP") (pintype "input"))
    )
    (net (code "3") (name "ALERT") (class "Default")
      (node (ref "P1.01/2.4B") (pin "P$J24") (pinfunction "P0.10/NFC2_P$J24") (pintype "bidirectional"))
      (node (ref "U1") (pin "5") (pinfunction "~{ALERT}_5") (pintype "output"))
    )
    (net (code "4") (name "D+") (class "Default")
      (node (ref "D4") (pin "4") (pinfunction "I/O2_2_4") (pintype "bidirectional"))
      (node (ref "P1.01/2.4B") (pin "P$AD6") (pinfunction "D+_P$AD6") (pintype "bidirectional"))
    )
    (net (code "5") (name "D-") (class "Default")
      (node (ref "D4") (pin "6") (pinfunction "I/O1_2_6") (pintype "bidirectional"))
      (node (ref "P1.01/2.4B") (pin "P$AD4") (pinfunction "D-_P$AD4") (pintype "bidirectional"))
    )
    (net (code "6") (name "DN") (class "Default")
      (node (ref "D4") (pin "1") (pinfunction "I/O1_1_1") (pintype "bidirectional"))
      (node (ref "J3") (pin "A7") (pinfunction "DN1_A7") (pintype "bidirectional"))
      (node (ref "J3") (pin "B7") (pinfunction "DN2_B7") (pintype "bidirectional"))
    )
    (net (code "7") (name "DP") (class "Default")
      (node (ref "D4") (pin "3") (pinfunction "I/O2_1_3") (pintype "bidirectional"))
      (node (ref "J3") (pin "A6") (pinfunction "DP1_A6") (pintype "bidirectional"))
      (node (ref "J3") (pin "B6") (pinfunction "DP2_B6") (pintype "bidirectional"))
    )
    (net (code "8") (name "EPD_3V3") (class "Default")
      (node (ref "C1-EP-DR") (pin "1") (pinfunction "1_1") (pintype "passive"))
      (node (ref "EPD_C5") (pin "2") (pinfunction "2_2") (pintype "passive"))
      (node (ref "J2") (pin "15") (pinfunction "15_15") (pintype "bidirectional"))
      (node (ref "J2") (pin "16") (pinfunction "16_16") (pintype "bidirectional"))
      (node (ref "L2") (pin "2") (pinfunction "2_2") (pintype "passive"))
      (node (ref "Q1") (pin "3") (pinfunction "D_3") (pintype "bidirectional"))
    )
    (net (code "9") (name "EPD_BUSY") (class "Default")
      (node (ref "J2") (pin "9") (pinfunction "9_9") (pintype "bidirectional"))
      (node (ref "P1.01/2.4B") (pin "P$AD12") (pinfunction "P0.17_P$AD12") (pintype "bidirectional"))
    )
    (net (code "10") (name "EPD_CS") (class "Default")
      (node (ref "J2") (pin "12") (pinfunction "12_12") (pintype "bidirectional"))
      (node (ref "P1.01/2.4B") (pin "P$K2") (pinfunction "P0.05/AIN3_P$K2") (pintype "bidirectional"))
    )
    (net (code "11") (name "EPD_DC") (class "Default")
      (node (ref "J2") (pin "11") (pinfunction "11_11") (pintype "bidirectional"))
      (node (ref "P1.01/2.4B") (pin "P$AD10") (pinfunction "P0.15_P$AD10") (pintype "bidirectional"))
    )
    (net (code "12") (name "EPD_RST") (class "Default")
      (node (ref "J2") (pin "10") (pinfunction "10_10") (pintype "bidirectional"))
      (node (ref "P1.01/2.4B") (pin "P$AC11") (pinfunction "P0.16_P$AC11") (pintype "bidirectional"))
    )
    (net (code "13") (name "GDR") (class "Default")
      (node (ref "J2") (pin "2") (pinfunction "2_2") (pintype "bidirectional"))
      (node (ref "Q2") (pin "1") (pinfunction "G_1") (pintype "bidirectional"))
      (node (ref "R6") (pin "2") (pinfunction "2_2") (pintype "bidirectional"))
    )
    (net (code "14") (name "GND") (class "Default")
      (node (ref "C1-EP-DR") (pin "2") (pinfunction "2_2") (pintype "passive"))
      (node (ref "C10") (pin "1") (pinfunction "1_1") (pintype "passive"))
      (node (ref "C11") (pin "1") (pinfunction "1_1") (pintype "passive"))
      (node (ref "C12") (pin "2") (pinfunction "2_2") (pintype "passive"))
      (node (ref "C13") (pin "2") (pinfunction "2_2") (pintype "passive"))
      (node (ref "C15") (pin "2") (pinfunction "2_2") (pintype "passive"))
      (node (ref "C16") (pin "2") (pinfunction "2_2") (pintype "passive"))
      (node (ref "C17") (pin "2") (pinfunction "2_2") (pintype "passive"))
      (node (ref "C18") (pin "2") (pinfunction "2_2") (pintype "passive"))
      (node (ref "C2") (pin "1") (pinfunction "1_1") (pintype "passive"))
      (node (ref "C20") (pin "1") (pinfunction "1_1") (pintype "passive"))
      (node (ref "C21") (pin "2") (pinfunction "2_2") (pintype "passive"))
      (node (ref "C23") (pin "1") (pinfunction "1_1") (pintype "passive"))
      (node (ref "C24") (pin "1") (pinfunction "1_1") (pintype "passive"))
      (node (ref "C25") (pin "2") (pinfunction "2_2") (pintype "passive"))
      (node (ref "C3") (pin "1") (pinfunction "1_1") (pintype "passive"))
      (node (ref "C33") (pin "2") (pinfunction "2_2") (pintype "passive"))
      (node (ref "C37") (pin "2") (pinfunction "2_2") (pintype "passive"))
      (node (ref "C38") (pin "2") (pinfunction "2_2") (pintype "passive"))
      (node (ref "C39") (pin "2") (pinfunction "2_2") (pintype "passive"))
      (node (ref "C4") (pin "1") (pinfunction "1_1") (pintype "passive"))
      (node (ref "C42") (pin "1") (pinfunction "1_1") (pintype "passive"))
      (node (ref "C43") (pin "2") (pinfunction "2_2") (pintype "passive"))
      (node (ref "C5") (pin "1") (pinfunction "1_1") (pintype "passive"))
      (node (ref "C6") (pin "1") (pinfunction "1_1") (pintype "passive"))
      (node (ref "C7") (pin "2") (pinfunction "2_2") (pintype "passive"))
      (node (ref "C8") (pin "2") (pinfunction "2_2") (pintype "passive"))
      (node (ref "C9") (pin "2") (pinfunction "2_2") (pintype "passive"))
      (node (ref "CC1") (pin "2") (pinfunction "2_2") (pintype "passive"))
      (node (ref "CC10") (pin "2") (pinfunction "2_2") (pintype "passive"))
      (node (ref "CC11") (pin "2") (pinfunction "2_2") (pintype "passive"))
      (node (ref "CC14") (pin "1") (pinfunction "1_1") (pintype "passive"))
      (node (ref "CC19") (pin "2") (pinfunction "2_2") (pintype "passive"))
      (node (ref "CC2") (pin "2") (pinfunction "2_2") (pintype "passive"))
      (node (ref "CC22") (pin "1") (pinfunction "1_1") (pintype "passive"))
      (node (ref "CC3") (pin "1") (pinfunction "1_1") (pintype "passive"))
      (node (ref "CC4") (pin "1") (pinfunction "1_1") (pintype "passive"))
      (node (ref "CC5") (pin "1") (pinfunction "1_1") (pintype "passive"))
      (node (ref "D2") (pin "1") (pinfunction "K_1") (pintype "bidirectional"))
      (node (ref "D4") (pin "2") (pinfunction "GND_2") (pintype "bidirectional"))
      (node (ref "EPD_C1") (pin "1") (pinfunction "1_1") (pintype "passive"))
      (node (ref "EPD_C10") (pin "1") (pinfunction "1_1") (pintype "passive"))
      (node (ref "EPD_C11") (pin "1") (pinfunction "1_1") (pintype "passive"))
      (node (ref "EPD_C12") (pin "1") (pinfunction "1_1") (pintype "passive"))
      (node (ref "EPD_C2") (pin "1") (pinfunction "1_1") (pintype "passive"))
      (node (ref "EPD_C5") (pin "1") (pinfunction "1_1") (pintype "passive"))
      (node (ref "EPD_C6") (pin "1") (pinfunction "1_1") (pintype "passive"))
      (node (ref "EPD_C7") (pin "1") (pinfunction "1_1") (pintype "passive"))
      (node (ref "EPD_C8") (pin "1") (pinfunction "1_1") (pintype "passive"))
      (node (ref "EPD_C9") (pin "1") (pinfunction "1_1") (pintype "passive"))
      (node (ref "IC1") (pin "D2") (pinfunction "GND_D2") (pintype "bidirectional"))
      (node (ref "IC2") (pin "B1") (pinfunction "VSEL_B1") (pintype "bidirectional"))
      (node (ref "IC2") (pin "C1") (pinfunction "AGND_C1") (pintype "bidirectional"))
      (node (ref "IC2") (pin "C2") (pinfunction "PGND_1_C2") (pintype "bidirectional"))
      (node (ref "IC2") (pin "C3") (pinfunction "PGND_2_C3") (pintype "bidirectional"))
      (node (ref "IC3") (pin "8") (pinfunction "GNDIO_8") (pintype "bidirectional"))
      (node (ref "IC3") (pin "9") (pinfunction "GND_9") (pintype "bidirectional"))
      (node (ref "IC4") (pin "B1") (pinfunction "IN/TRIG_B1") (pintype "bidirectional"))
      (node (ref "IC4") (pin "B3") (pinfunction "GND_B3") (pintype "bidirectional"))
      (node (ref "J1") (pin "3") (pinfunction "3_3") (pintype "bidirectional"))
      (node (ref "J1") (pin "5") (pinfunction "5_5") (pintype "bidirectional"))
      (node (ref "J2") (pin "17") (pinfunction "17_17") (pintype "bidirectional"))
      (node (ref "J2") (pin "8") (pinfunction "8_8") (pintype "bidirectional"))
      (node (ref "J2") (pin "MP1") (pinfunction "MP1_MP1") (pintype "bidirectional"))
      (node (ref "J2") (pin "MP2") (pinfunction "MP2_MP2") (pintype "bidirectional"))
      (node (ref "J3") (pin "A12_B1") (pinfunction "GND_A12_B1") (pintype "power_in"))
      (node (ref "J3") (pin "A1_B12") (pinfunction "GND_A1_B12") (pintype "power_in"))
      (node (ref "J3") (pin "SH1") (pinfunction "SHIELD_SH1") (pintype "passive"))
      (node (ref "J3") (pin "SH2") (pinfunction "SHIELD_SH2") (pintype "passive"))
      (node (ref "J3") (pin "SH3") (pinfunction "SHIELD_SH3") (pintype "passive"))
      (node (ref "J3") (pin "SH4") (pinfunction "SHIELD_SH4") (pintype "passive"))
      (node (ref "P1.01/2.4B") (pin "P$74") (pinfunction "VSS_PAD_P$74") (pintype "bidirectional"))
      (node (ref "P1.01/2.4B") (pin "P$75") (pinfunction "VSS_PAD_P$75") (pintype "bidirectional"))
      (node (ref "P1.01/2.4B") (pin "P$76") (pinfunction "VSS_PAD_P$76") (pintype "bidirectional"))
      (node (ref "P1.01/2.4B") (pin "P$77") (pinfunction "VSS_PAD_P$77") (pintype "bidirectional"))
      (node (ref "P1.01/2.4B") (pin "P$78") (pinfunction "VSS_PAD_P$78") (pintype "bidirectional"))
      (node (ref "P1.01/2.4B") (pin "P$79") (pinfunction "VSS_PAD_P$79") (pintype "bidirectional"))
      (node (ref "P1.01/2.4B") (pin "P$80") (pinfunction "VSS_PAD_P$80") (pintype "bidirectional"))
      (node (ref "P1.01/2.4B") (pin "P$81") (pinfunction "VSS_PAD_P$81") (pintype "bidirectional"))
      (node (ref "P1.01/2.4B") (pin "P$82") (pinfunction "VSS_PAD_P$82") (pintype "bidirectional"))
      (node (ref "P1.01/2.4B") (pin "P$83") (pinfunction "VSS_PAD_P$83") (pintype "bidirectional"))
      (node (ref "P1.01/2.4B") (pin "P$84") (pinfunction "VSS_PAD_P$84") (pintype "bidirectional"))
      (node (ref "P1.01/2.4B") (pin "P$85") (pinfunction "VSS_PAD_P$85") (pintype "bidirectional"))
      (node (ref "P1.01/2.4B") (pin "P$86") (pinfunction "VSS_PAD_P$86") (pintype "bidirectional"))
      (node (ref "P1.01/2.4B") (pin "P$87") (pinfunction "VSS_PAD_P$87") (pintype "bidirectional"))
      (node (ref "P1.01/2.4B") (pin "P$88") (pinfunction "VSS_PAD_P$88") (pintype "bidirectional"))
      (node (ref "P1.01/2.4B") (pin "P$89") (pinfunction "VSS_PAD_P$89") (pintype "bidirectional"))
      (node (ref "P1.01/2.4B") (pin "P$90") (pinfunction "VSS_PAD_P$90") (pintype "bidirectional"))
      (node (ref "P1.01/2.4B") (pin "P$B7") (pinfunction "VSS_P$B7") (pintype "power_in"))
      (node (ref "P1.01/2.4B") (pin "P$F23") (pinfunction "VSS_PA_P$F23") (pintype "bidirectional"))
      (node (ref "R1") (pin "1") (pinfunction "1_1") (pintype "bidirectional"))
      (node (ref "R10") (pin "1") (pinfunction "1_1") (pintype "bidirectional"))
      (node (ref "R14") (pin "2") (pinfunction "2_2") (pintype "bidirectional"))
      (node (ref "R15") (pin "1") (pinfunction "1_1") (pintype "bidirectional"))
      (node (ref "R6") (pin "1") (pinfunction "1_1") (pintype "bidirectional"))
      (node (ref "R8") (pin "2") (pinfunction "2_2") (pintype "bidirectional"))
      (node (ref "SJ1") (pin "1") (pinfunction "1_1") (pintype "passive"))
      (node (ref "SW1") (pin "1") (pinfunction "1_1") (pintype "passive"))
      (node (ref "SW2") (pin "1") (pinfunction "1_1") (pintype "passive"))
      (node (ref "SW3") (pin "1") (pinfunction "1_1") (pintype "passive"))
      (node (ref "TP_SDA10") (pin "TP") (pinfunction "TP_TP") (pintype "input"))
      (node (ref "TP_SDA6") (pin "TP") (pinfunction "TP_TP") (pintype "input"))
      (node (ref "U1") (pin "1") (pinfunction "CTG_1") (pintype "power_in"))
      (node (ref "U1") (pin "4") (pinfunction "GND_4") (pintype "power_in"))
      (node (ref "U1") (pin "6") (pinfunction "QSTRT_6") (pintype "input"))
      (node (ref "U1") (pin "9") (pinfunction "EP_9") (pintype "power_in"))
      (node (ref "X1") (pin "2") (pinfunction "2_2") (pintype "passive"))
      (node (ref "X1") (pin "4") (pinfunction "4_4") (pintype "passive"))
    )
    (net (code "15") (name "HAPTIC_EN") (class "Default")
      (node (ref "IC4") (pin "A1") (pinfunction "EN_A1") (pintype "bidirectional"))
      (node (ref "P1.01/2.4B") (pin "P$U1") (pinfunction "P0.12_P$U1") (pintype "bidirectional"))
    )
    (net (code "16") (name "IMU_INT1") (class "Default")
      (node (ref "IC3") (pin "5") (pinfunction "INT1_5") (pintype "bidirectional"))
      (node (ref "P1.01/2.4B") (pin "P$N1") (pinfunction "P0.08_P$N1") (pintype "bidirectional"))
    )
    (net (code "17") (name "IMU_INT2") (class "Default")
      (node (ref "IC3") (pin "6") (pinfunction "INT2_6") (pintype "bidirectional"))
      (node (ref "P1.01/2.4B") (pin "P$P2") (pinfunction "P1.08_P$P2") (pintype "bidirectional"))
    )
    (net (code "18") (name "LX1") (class "Default")
      (node (ref "IC2") (pin "B2") (pinfunction "SW1_1_B2") (pintype "bidirectional"))
      (node (ref "IC2") (pin "B3") (pinfunction "SW1_2_B3") (pintype "bidirectional"))
      (node (ref "L1") (pin "1") (pinfunction "1_1") (pintype "bidirectional"))
    )
    (net (code "19") (name "LX2") (class "Default")
      (node (ref "IC2") (pin "D2") (pinfunction "SW2_1_D2") (pintype "bidirectional"))
      (node (ref "IC2") (pin "D3") (pinfunction "SW2_2_D3") (pintype "bidirectional"))
      (node (ref "L1") (pin "2") (pinfunction "2_2") (pintype "bidirectional"))
    )
    (net (code "20") (name "MOSI") (class "Default")
      (node (ref "J2") (pin "14") (pinfunction "14_14") (pintype "bidirectional"))
      (node (ref "P1.01/2.4B") (pin "P$B13") (pinfunction "P0.03/AIN1_P$B13") (pintype "bidirectional"))
    )
    (net (code "21") (name "Net-(ANT1-FEED)") (class "Default")
      (node (ref "ANT1") (pin "1") (pinfunction "FEED_1") (pintype "input"))
      (node (ref "CC22") (pin "2") (pinfunction "2_2") (pintype "passive"))
      (node (ref "CC4") (pin "2") (pinfunction "2_2") (pintype "passive"))
      (node (ref "LL1") (pin "2") (pinfunction "2_2") (pintype "passive"))
    )
    (net (code "22") (name "Net-(C5-Pad2)") (class "Default")
      (node (ref "C5") (pin "2") (pinfunction "2_2") (pintype "passive"))
      (node (ref "R11") (pin "1") (pinfunction "1_1") (pintype "bidirectional"))
    )
    (net (code "23") (name "Net-(C10-Pad2)") (class "Default")
      (node (ref "C10") (pin "2") (pinfunction "2_2") (pintype "passive"))
      (node (ref "R12") (pin "1") (pinfunction "1_1") (pintype "bidirectional"))
    )
    (net (code "24") (name "Net-(C11-Pad2)") (class "Default")
      (node (ref "C11") (pin "2") (pinfunction "2_2") (pintype "passive"))
      (node (ref "R13") (pin "1") (pinfunction "1_1") (pintype "bidirectional"))
    )
    (net (code "25") (name "Net-(C12-Pad1)") (class "Default")
      (node (ref "C12") (pin "1") (pinfunction "1_1") (pintype "passive"))
      (node (ref "P1.01/2.4B") (pin "P$A22") (pinfunction "VDD_P$A22") (pintype "power_in"))
    )
    (net (code "26") (name "Net-(D1-K)") (class "Default")
      (node (ref "C2-EP-DR") (pin "1") (pinfunction "1_1") (pintype "passive"))
      (node (ref "D1") (pin "1") (pinfunction "K_1") (pintype "bidirectional"))
      (node (ref "D2") (pin "2") (pinfunction "A_2") (pintype "bidirectional"))
    )
    (net (code "27") (name "Net-(D3-A)") (class "Default")
      (node (ref "C2-EP-DR") (pin "2") (pinfunction "2_2") (pintype "passive"))
      (node (ref "D3") (pin "2") (pinfunction "A_2") (pintype "bidirectional"))
      (node (ref "L2") (pin "1") (pinfunction "1_1") (pintype "passive"))
      (node (ref "Q2") (pin "3") (pinfunction "D_3") (pintype "bidirectional"))
    )
    (net (code "28") (name "Net-(EPD_C1-Pad2)") (class "Default")
      (node (ref "EPD_C1") (pin "2") (pinfunction "2_2") (pintype "passive"))
      (node (ref "J2") (pin "5") (pinfunction "5_5") (pintype "bidirectional"))
    )
    (net (code "29") (name "Net-(EPD_C2-Pad2)") (class "Default")
      (node (ref "EPD_C2") (pin "2") (pinfunction "2_2") (pintype "passive"))
      (node (ref "J2") (pin "4") (pinfunction "4_4") (pintype "bidirectional"))
    )
    (net (code "30") (name "Net-(EPD_C6-Pad2)") (class "Default")
      (node (ref "EPD_C6") (pin "2") (pinfunction "2_2") (pintype "passive"))
      (node (ref "J2") (pin "18") (pinfunction "18_18") (pintype "bidirectional"))
    )
    (net (code "31") (name "Net-(EPD_C7-Pad2)") (class "Default")
      (node (ref "EPD_C7") (pin "2") (pinfunction "2_2") (pintype "passive"))
      (node (ref "J2") (pin "19") (pinfunction "19_19") (pintype "bidirectional"))
    )
    (net (code "32") (name "Net-(EPD_C8-Pad2)") (class "Default")
      (node (ref "EPD_C8") (pin "2") (pinfunction "2_2") (pintype "passive"))
      (node (ref "J2") (pin "20") (pinfunction "20_20") (pintype "bidirectional"))
    )
    (net (code "33") (name "Net-(EPD_C10-Pad2)") (class "Default")
      (node (ref "EPD_C10") (pin "2") (pinfunction "2_2") (pintype "passive"))
      (node (ref "J2") (pin "22") (pinfunction "22_22") (pintype "bidirectional"))
    )
    (net (code "34") (name "Net-(EPD_C12-Pad2)") (class "Default")
      (node (ref "EPD_C12") (pin "2") (pinfunction "2_2") (pintype "passive"))
      (node (ref "J2") (pin "24") (pinfunction "24_24") (pintype "bidirectional"))
    )
    (net (code "35") (name "Net-(IC1-TS{slash}MR)") (class "Default")
      (node (ref "IC1") (pin "D1") (pinfunction "TS/MR_D1") (pintype "bidirectional"))
      (node (ref "R1") (pin "2") (pinfunction "2_2") (pintype "bidirectional"))
    )
    (net (code "36") (name "Net-(IC2-SCL)") (class "Default")
      (node (ref "IC2") (pin "D1") (pinfunction "SCL_D1") (pintype "bidirectional"))
      (node (ref "R2") (pin "2") (pinfunction "2_2") (pintype "bidirectional"))
    )
    (net (code "37") (name "Net-(IC2-SDA)") (class "Default")
      (node (ref "IC2") (pin "E1") (pinfunction "SDA_E1") (pintype "bidirectional"))
      (node (ref "R3") (pin "2") (pinfunction "2_2") (pintype "bidirectional"))
    )
    (net (code "38") (name "Net-(IC3-SDO)") (class "Default")
      (node (ref "IC3") (pin "1") (pinfunction "SDO_1") (pintype "bidirectional"))
      (node (ref "R8") (pin "1") (pinfunction "1_1") (pintype "bidirectional"))
    )
    (net (code "39") (name "Net-(IC4-REG)") (class "Default")
      (node (ref "C3") (pin "2") (pinfunction "2_2") (pintype "passive"))
      (node (ref "IC4") (pin "A2") (pinfunction "REG_A2") (pintype "bidirectional"))
    )
    (net (code "40") (name "Net-(J3-CC1)") (class "Default")
      (node (ref "J3") (pin "A5") (pinfunction "CC1_A5") (pintype "bidirectional"))
      (node (ref "R14") (pin "1") (pinfunction "1_1") (pintype "bidirectional"))
    )
    (net (code "41") (name "Net-(J3-CC2)") (class "Default")
      (node (ref "J3") (pin "B5") (pinfunction "CC2_B5") (pintype "bidirectional"))
      (node (ref "R15") (pin "2") (pinfunction "2_2") (pintype "bidirectional"))
    )
    (net (code "42") (name "Net-(LL2-Pad1)") (class "Default")
      (node (ref "LL2") (pin "1") (pinfunction "1_1") (pintype "passive"))
      (node (ref "LL3") (pin "2") (pinfunction "2_2") (pintype "passive"))
    )
    (net (code "43") (name "Net-(P1.01/2.4B-ANT)") (class "Default")
      (node (ref "CC3") (pin "2") (pinfunction "2_2") (pintype "passive"))
      (node (ref "LL1") (pin "1") (pinfunction "1_1") (pintype "passive"))
      (node (ref "P1.01/2.4B") (pin "P$H23") (pinfunction "ANT_P$H23") (pintype "bidirectional"))
    )
    (net (code "44") (name "Net-(P1.01/2.4B-DCC)") (class "Default")
      (node (ref "LL2") (pin "2") (pinfunction "2_2") (pintype "passive"))
      (node (ref "P1.01/2.4B") (pin "P$B3") (pinfunction "DCC_P$B3") (pintype "output"))
    )
    (net (code "45") (name "Net-(P1.01/2.4B-DEC1)") (class "Default")
      (node (ref "CC5") (pin "2") (pinfunction "2_2") (pintype "passive"))
      (node (ref "P1.01/2.4B") (pin "P$C1") (pinfunction "DEC1_P$C1") (pintype "power_in"))
    )
    (net (code "46") (name "Net-(P1.01/2.4B-DEC2)") (class "Default")
      (node (ref "C13") (pin "1") (pinfunction "1_1") (pintype "passive"))
      (node (ref "P1.01/2.4B") (pin "P$A18") (pinfunction "DEC2_P$A18") (pintype "bidirectional"))
    )
    (net (code "47") (name "Net-(P1.01/2.4B-DEC3)") (class "Default")
      (node (ref "CC11") (pin "1") (pinfunction "1_1") (pintype "passive"))
      (node (ref "P1.01/2.4B") (pin "P$D23") (pinfunction "DEC3_P$D23") (pintype "bidirectional"))
    )
    (net (code "48") (name "Net-(P1.01/2.4B-DEC3V3)") (class "Default")
      (node (ref "C20") (pin "2") (pinfunction "2_2") (pintype "passive"))
      (node (ref "P1.01/2.4B") (pin "P$AC5") (pinfunction "DEC3V3_P$AC5") (pintype "bidirectional"))
    )
    (net (code "49") (name "Net-(P1.01/2.4B-DEC4)") (class "Default")
      (node (ref "C15") (pin "1") (pinfunction "1_1") (pintype "passive"))
      (node (ref "C16") (pin "1") (pinfunction "1_1") (pintype "passive"))
      (node (ref "CC10") (pin "1") (pinfunction "1_1") (pintype "passive"))
      (node (ref "LL3") (pin "1") (pinfunction "1_1") (pintype "passive"))
      (node (ref "P1.01/2.4B") (pin "P$B5") (pinfunction "DEC4_P$B5") (pintype "power_in"))
      (node (ref "P1.01/2.4B") (pin "P$E24") (pinfunction "DEC6_P$E24") (pintype "bidirectional"))
    )
    (net (code "50") (name "Net-(P1.01/2.4B-DEC5)") (class "Default")
      (node (ref "C9") (pin "1") (pinfunction "1_1") (pintype "passive"))
      (node (ref "P1.01/2.4B") (pin "P$N24") (pinfunction "DEC5_P$N24") (pintype "bidirectional"))
    )
    (net (code "51") (name "Net-(P1.01/2.4B-P0.00{slash}XL1)") (class "Default")
      (node (ref "C17") (pin "1") (pinfunction "1_1") (pintype "passive"))
      (node (ref "P1.01/2.4B") (pin "P$D2") (pinfunction "P0.00/XL1_P$D2") (pintype "bidirectional"))
      (node (ref "X2") (pin "2") (pinfunction "2_2") (pintype "passive"))
    )
    (net (code "52") (name "Net-(P1.01/2.4B-P0.01{slash}XL2)") (class "Default")
      (node (ref "C18") (pin "1") (pinfunction "1_1") (pintype "passive"))
      (node (ref "P1.01/2.4B") (pin "P$F2") (pinfunction "P0.01/XL2_P$F2") (pintype "bidirectional"))
      (node (ref "X2") (pin "1") (pinfunction "1_1") (pintype "passive"))
    )
    (net (code "53") (name "Net-(P1.01/2.4B-XC1)") (class "Default")
      (node (ref "CC1") (pin "1") (pinfunction "1_1") (pintype "passive"))
      (node (ref "P1.01/2.4B") (pin "P$B24") (pinfunction "XC1_P$B24") (pintype "input"))
      (node (ref "X1") (pin "1") (pinfunction "1_1") (pintype "passive"))
    )
    (net (code "54") (name "Net-(P1.01/2.4B-XC2)") (class "Default")
      (node (ref "CC2") (pin "1") (pinfunction "1_1") (pintype "passive"))
      (node (ref "P1.01/2.4B") (pin "P$A23") (pinfunction "XC2_P$A23") (pintype "output"))
      (node (ref "X1") (pin "3") (pinfunction "3_3") (pintype "passive"))
    )
    (net (code "55") (name "Net-(Q2-S)") (class "Default")
      (node (ref "Q2") (pin "2") (pinfunction "S_2") (pintype "bidirectional"))
      (node (ref "R9") (pin "2") (pinfunction "2_2") (pintype "bidirectional"))
    )
    (net (code "56") (name "Net-(R10-Pad2)") (class "Default")
      (node (ref "R10") (pin "2") (pinfunction "2_2") (pintype "bidirectional"))
      (node (ref "R9") (pin "1") (pinfunction "1_1") (pintype "bidirectional"))
      (node (ref "SJ1") (pin "2") (pinfunction "2_2") (pintype "passive"))
    )
    (net (code "57") (name "OUT+") (class "Default")
      (node (ref "IC4") (pin "A3") (pinfunction "OUT+_A3") (pintype "bidirectional"))
      (node (ref "TP_SDA7") (pin "TP") (pinfunction "TP_TP") (pintype "input"))
    )
    (net (code "58") (name "OUT-") (class "Default")
      (node (ref "IC4") (pin "C3") (pinfunction "OUT-_C3") (pintype "bidirectional"))
      (node (ref "TP_SDA8") (pin "TP") (pinfunction "TP_TP") (pintype "input"))
    )
    (net (code "59") (name "P0.04") (class "Default")
      (node (ref "P1.01/2.4B") (pin "P$J1") (pinfunction "P0.04/AIN2_P$J1") (pintype "bidirectional"))
    )
    (net (code "60") (name "P0.09") (class "Default")
      (node (ref "P1.01/2.4B") (pin "P$L24") (pinfunction "P0.09/NFC1_P$L24") (pintype "bidirectional"))
    )
    (net (code "61") (name "P0.13") (class "Default")
      (node (ref "P1.01/2.4B") (pin "P$AD8") (pinfunction "P0.13_P$AD8") (pintype "bidirectional"))
      (node (ref "SW1") (pin "2") (pinfunction "2_2") (pintype "passive"))
    )
    (net (code "62") (name "P0.14") (class "Default")
      (node (ref "P1.01/2.4B") (pin "P$AC9") (pinfunction "P0.14_P$AC9") (pintype "bidirectional"))
      (node (ref "SW2") (pin "2") (pinfunction "2_2") (pintype "passive"))
    )
    (net (code "63") (name "P0.19") (class "Default")
      (node (ref "P1.01/2.4B") (pin "P$AC15") (pinfunction "P0.19_P$AC15") (pintype "bidirectional"))
    )
    (net (code "64") (name "P0.20") (class "Default")
      (node (ref "P1.01/2.4B") (pin "P$AD16") (pinfunction "P0.20_P$AD16") (pintype "bidirectional"))
    )
    (net (code "65") (name "P0.21") (class "Default")
      (node (ref "P1.01/2.4B") (pin "P$AC17") (pinfunction "P0.21_P$AC17") (pintype "bidirectional"))
    )
    (net (code "66") (name "P0.22") (class "Default")
      (node (ref "P1.01/2.4B") (pin "P$AD18") (pinfunction "P0.22_P$AD18") (pintype "bidirectional"))
    )
    (net (code "67") (name "P0.23") (class "Default")
      (node (ref "P1.01/2.4B") (pin "P$AC19") (pinfunction "P0.23_P$AC19") (pintype "bidirectional"))
    )
    (net (code "68") (name "P0.24") (class "Default")
      (node (ref "P1.01/2.4B") (pin "P$AD20") (pinfunction "P0.24_P$AD20") (pintype "bidirectional"))
    )
    (net (code "69") (name "P0.25") (class "Default")
      (node (ref "P1.01/2.4B") (pin "P$AC21") (pinfunction "P0.25_P$AC21") (pintype "bidirectional"))
    )
    (net (code "70") (name "P0.26") (class "Default")
      (node (ref "P1.01/2.4B") (pin "P$G1") (pinfunction "P0.26_P$G1") (pintype "bidirectional"))
    )
    (net (code "71") (name "P0.27") (class "Default")
      (node (ref "P1.01/2.4B") (pin "P$H2") (pinfunction "P0.27_P$H2") (pintype "bidirectional"))
    )
    (net (code "72") (name "P0.28") (class "Default")
      (node (ref "P1.01/2.4B") (pin "P$B11") (pinfunction "P0.28/AIN4_P$B11") (pintype "bidirectional"))
    )
    (net (code "73") (name "P0.29") (class "Default")
      (node (ref "P1.01/2.4B") (pin "P$A10") (pinfunction "P0.29/AIN5_P$A10") (pintype "bidirectional"))
    )
    (net (code "74") (name "P0.30") (class "Default")
      (node (ref "P1.01/2.4B") (pin "P$B9") (pinfunction "P0.30/AIN6_P$B9") (pintype "bidirectional"))
    )
    (net (code "75") (name "P0.31") (class "Default")
      (node (ref "P1.01/2.4B") (pin "P$A8") (pinfunction "P0.31/AIN7_P$A8") (pintype "bidirectional"))
    )
    (net (code "76") (name "P1.01") (class "Default")
      (node (ref "P1.01/2.4B") (pin "P$Y23") (pinfunction "P1.01_P$Y23") (pintype "bidirectional"))
      (node (ref "Q1") (pin "1") (pinfunction "G_1") (pintype "bidirectional"))
      (node (ref "R7") (pin "1") (pinfunction "1_1") (pintype "bidirectional"))
    )
    (net (code "77") (name "P1.02") (class "Default")
      (node (ref "P1.01/2.4B") (pin "P$W24") (pinfunction "P1.02_P$W24") (pintype "bidirectional"))
      (node (ref "SW3") (pin "2") (pinfunction "2_2") (pintype "passive"))
    )
    (net (code "78") (name "P1.03") (class "Default")
      (node (ref "P1.01/2.4B") (pin "P$V23") (pinfunction "P1.03_P$V23") (pintype "bidirectional"))
    )
    (net (code "79") (name "P1.04") (class "Default")
      (node (ref "P1.01/2.4B") (pin "P$U24") (pinfunction "P1.04_P$U24") (pintype "bidirectional"))
    )
    (net (code "80") (name "P1.05") (class "Default")
      (node (ref "P1.01/2.4B") (pin "P$T23") (pinfunction "P1.05_P$T23") (pintype "bidirectional"))
    )
    (net (code "81") (name "P1.06") (class "Default")
      (node (ref "P1.01/2.4B") (pin "P$R24") (pinfunction "P1.06_P$R24") (pintype "bidirectional"))
    )
    (net (code "82") (name "P1.07") (class "Default")
      (node (ref "P1.01/2.4B") (pin "P$P23") (pinfunction "P1.07_P$P23") (pintype "bidirectional"))
    )
    (net (code "83") (name "P1.09") (class "Default")
      (node (ref "P1.01/2.4B") (pin "P$R1") (pinfunction "P1.09_P$R1") (pintype "bidirectional"))
    )
    (net (code "84") (name "P1.10") (class "Default")
      (node (ref "P1.01/2.4B") (pin "P$A20") (pinfunction "P1.10_P$A20") (pintype "bidirectional"))
    )
    (net (code "85") (name "P1.11") (class "Default")
      (node (ref "P1.01/2.4B") (pin "P$B19") (pinfunction "P1.11_P$B19") (pintype "bidirectional"))
    )
    (net (code "86") (name "P1.12") (class "Default")
      (node (ref "P1.01/2.4B") (pin "P$B17") (pinfunction "P1.12_P$B17") (pintype "bidirectional"))
    )
    (net (code "87") (name "P1.13") (class "Default")
      (node (ref "P1.01/2.4B") (pin "P$A16") (pinfunction "P1.13_P$A16") (pintype "bidirectional"))
    )
    (net (code "88") (name "P1.14") (class "Default")
      (node (ref "P1.01/2.4B") (pin "P$B15") (pinfunction "P1.14_P$B15") (pintype "bidirectional"))
    )
    (net (code "89") (name "P1.15") (class "Default")
      (node (ref "P1.01/2.4B") (pin "P$A14") (pinfunction "P1.15_P$A14") (pintype "bidirectional"))
    )
    (net (code "90") (name "PMIC_INT") (class "Default")
      (node (ref "IC1") (pin "A1") (pinfunction "~{INT}_A1") (pintype "bidirectional"))
      (node (ref "P1.01/2.4B") (pin "P$T2") (pinfunction "P0.11_P$T2") (pintype "bidirectional"))
    )
    (net (code "91") (name "PREVGH") (class "Default")
      (node (ref "D3") (pin "1") (pinfunction "K_1") (pintype "bidirectional"))
      (node (ref "EPD_C9") (pin "2") (pinfunction "2_2") (pintype "passive"))
      (node (ref "J2") (pin "21") (pinfunction "21_21") (pintype "bidirectional"))
    )
    (net (code "92") (name "PREVGL") (class "Default")
      (node (ref "D1") (pin "2") (pinfunction "A_2") (pintype "bidirectional"))
      (node (ref "EPD_C11") (pin "2") (pinfunction "2_2") (pintype "passive"))
      (node (ref "J2") (pin "23") (pinfunction "23_23") (pintype "bidirectional"))
    )
    (net (code "93") (name "RESE") (class "Default")
      (node (ref "J2") (pin "3") (pinfunction "3_3") (pintype "bidirectional"))
    )
    (net (code "94") (name "RESET") (class "Default")
      (node (ref "J1") (pin "6") (pinfunction "6_6") (pintype "bidirectional"))
      (node (ref "P1.01/2.4B") (pin "P$AC13") (pinfunction "P0.18/RESET_P$AC13") (pintype "bidirectional"))
      (node (ref "TP_SDA4") (pin "TP") (pinfunction "TP_TP") (pintype "input"))
    )
    (net (code "95") (name "SCK") (class "Default")
      (node (ref "J2") (pin "13") (pinfunction "13_13") (pintype "bidirectional"))
      (node (ref "P1.01/2.4B") (pin "P$A12") (pinfunction "P0.02/AIN0_P$A12") (pintype "bidirectional"))
    )
    (net (code "96") (name "SCL{slash}1.4C") (class "Default")
      (node (ref "IC4") (pin "C1") (pinfunction "SCL_C1") (pintype "bidirectional"))
      (node (ref "U1") (pin "7") (pinfunction "SCL_7") (pintype "input"))
    )
    (net (code "97") (name "SCL{slash}2.4C") (class "Default")
      (node (ref "IC1") (pin "B1") (pinfunction "SCL_B1") (pintype "bidirectional"))
      (node (ref "IC3") (pin "12") (pinfunction "SCX_12") (pintype "bidirectional"))
      (node (ref "P1.01/2.4B") (pin "P$M2") (pinfunction "P0.07_P$M2") (pintype "bidirectional"))
      (node (ref "R2") (pin "1") (pinfunction "1_1") (pintype "bidirectional"))
      (node (ref "R4") (pin "1") (pinfunction "1_1") (pintype "bidirectional"))
      (node (ref "TP_SCL") (pin "TP") (pinfunction "TP_TP") (pintype "input"))
    )
    (net (code "98") (name "SDA{slash}1.4C") (class "Default")
      (node (ref "IC4") (pin "B2") (pinfunction "SDA_B2") (pintype "bidirectional"))
      (node (ref "U1") (pin "8") (pinfunction "SDA_8") (pintype "bidirectional"))
    )
    (net (code "99") (name "SDA{slash}2.4C") (class "Default")
      (node (ref "IC1") (pin "C1") (pinfunction "SDA_C1") (pintype "bidirectional"))
      (node (ref "IC3") (pin "2") (pinfunction "SDX_2") (pintype "bidirectional"))
      (node (ref "P1.01/2.4B") (pin "P$L1") (pinfunction "P0.06_P$L1") (pintype "bidirectional"))
      (node (ref "R3") (pin "1") (pinfunction "1_1") (pintype "bidirectional"))
      (node (ref "R5") (pin "1") (pinfunction "1_1") (pintype "bidirectional"))
      (node (ref "TP_SDA") (pin "TP") (pinfunction "TP_TP") (pintype "input"))
    )
    (net (code "100") (name "SWDCLK") (class "Default")
      (node (ref "J1") (pin "4") (pinfunction "4_4") (pintype "bidirectional"))
      (node (ref "P1.01/2.4B") (pin "P$AA24") (pinfunction "SWDCLK_P$AA24") (pintype "input"))
      (node (ref "TP_SDA3") (pin "TP") (pinfunction "TP_TP") (pintype "input"))
    )
    (net (code "101") (name "SWDIO") (class "Default")
      (node (ref "J1") (pin "2") (pinfunction "2_2") (pintype "bidirectional"))
      (node (ref "P1.01/2.4B") (pin "P$AC24") (pinfunction "SWDIO_P$AC24") (pintype "bidirectional"))
      (node (ref "TP_SDA2") (pin "TP") (pinfunction "TP_TP") (pintype "input"))
    )
    (net (code "102") (name "SWO") (class "Default")
      (node (ref "P1.01/2.4B") (pin "P$AD22") (pinfunction "P1.00_P$AD22") (pintype "bidirectional"))
      (node (ref "TP_SDA1") (pin "TP") (pinfunction "TP_TP") (pintype "input"))
    )
    (net (code "103") (name "VBAT{slash}1.2A") (class "Default")
      (node (ref "C2") (pin "2") (pinfunction "2_2") (pintype "passive"))
      (node (ref "TP_SDA9") (pin "TP") (pinfunction "TP_TP") (pintype "input"))
      (node (ref "U1") (pin "2") (pinfunction "CELL_2") (pintype "power_in"))
      (node (ref "U1") (pin "3") (pinfunction "VDD_3") (pintype "power_in"))
    )
    (net (code "104") (name "VBAT{slash}2.5C") (class "Default")
      (node (ref "C37") (pin "1") (pinfunction "1_1") (pintype "passive"))
      (node (ref "IC1") (pin "C2") (pinfunction "BAT_C2") (pintype "bidirectional"))
    )
    (net (code "105") (name "VBUS{slash}1.5D") (class "Default")
      (node (ref "C42") (pin "2") (pinfunction "2_2") (pintype "passive"))
      (node (ref "C43") (pin "1") (pinfunction "1_1") (pintype "passive"))
      (node (ref "D4") (pin "5") (pinfunction "VBUS_5") (pintype "bidirectional"))
      (node (ref "J3") (pin "A4_B9") (pinfunction "VBUS_A4_B9") (pintype "power_in"))
      (node (ref "J3") (pin "A9_B4") (pinfunction "VBUS_A9_B4") (pintype "power_in"))
    )
    (net (code "106") (name "VBUS{slash}2.6D") (class "Default")
      (node (ref "C21") (pin "1") (pinfunction "1_1") (pintype "passive"))
      (node (ref "C38") (pin "1") (pinfunction "1_1") (pintype "passive"))
      (node (ref "IC1") (pin "A2") (pinfunction "IN_A2") (pintype "bidirectional"))
      (node (ref "P1.01/2.4B") (pin "P$AD2") (pinfunction "VBUS_P$AD2") (pintype "power_in"))
    )
    (net (code "107") (name "VREG") (class "Default")
      (node (ref "C23") (pin "2") (pinfunction "2_2") (pintype "passive"))
      (node (ref "C24") (pin "2") (pinfunction "2_2") (pintype "passive"))
      (node (ref "C39") (pin "1") (pinfunction "1_1") (pintype "passive"))
      (node (ref "IC1") (pin "B2") (pinfunction "SYS_B2") (pintype "bidirectional"))
      (node (ref "IC2") (pin "A1") (pinfunction "EN_A1") (pintype "bidirectional"))
      (node (ref "IC2") (pin "A2") (pinfunction "VIN_1_A2") (pintype "bidirectional"))
      (node (ref "IC2") (pin "A3") (pinfunction "VIN_2_A3") (pintype "bidirectional"))
      (node (ref "TP_VREG") (pin "TP") (pinfunction "TP_TP") (pintype "input"))
    )
    (net (code "108") (name "unconnected-(ANT1-NC-Pad2)") (class "Default")
      (node (ref "ANT1") (pin "2") (pinfunction "NC_2") (pintype "no_connect"))
    )
    (net (code "109") (name "unconnected-(IC3-ASCL-Pad11)") (class "Default")
      (node (ref "IC3") (pin "11") (pinfunction "ASCL_11") (pintype "bidirectional"))
    )
    (net (code "110") (name "unconnected-(IC3-ASDA-Pad4)") (class "Default")
      (node (ref "IC3") (pin "4") (pinfunction "ASDA_4") (pintype "bidirectional"))
    )
    (net (code "111") (name "unconnected-(J2-Pad1)") (class "Default")
      (node (ref "J2") (pin "1") (pinfunction "1_1") (pintype "bidirectional"))
    )
    (net (code "112") (name "unconnected-(J2-Pad6)") (class "Default")
      (node (ref "J2") (pin "6") (pinfunction "6_6") (pintype "bidirectional"))
    )
    (net (code "113") (name "unconnected-(J2-Pad7)") (class "Default")
      (node (ref "J2") (pin "7") (pinfunction "7_7") (pintype "bidirectional"))
    )
    (net (code "114") (name "unconnected-(J3-SBU1-PadA8)") (class "Default")
      (node (ref "J3") (pin "A8") (pinfunction "SBU1_A8") (pintype "bidirectional"))
    )
    (net (code "115") (name "unconnected-(J3-SBU2-PadB8)") (class "Default")
      (node (ref "J3") (pin "B8") (pinfunction "SBU2_B8") (pintype "bidirectional"))
    )
    (net (code "116") (name "unconnected-(P1.01/2.4B-DCCH-PadP$AB2)") (class "Default")
      (node (ref "P1.01/2.4B") (pin "P$AB2") (pinfunction "DCCH_P$AB2") (pintype "bidirectional"))
    )
  )
)
